# MAAV_RoombaShieldOnly_2V0.net
KiCad netlist of a schematic drawn in EAGLE
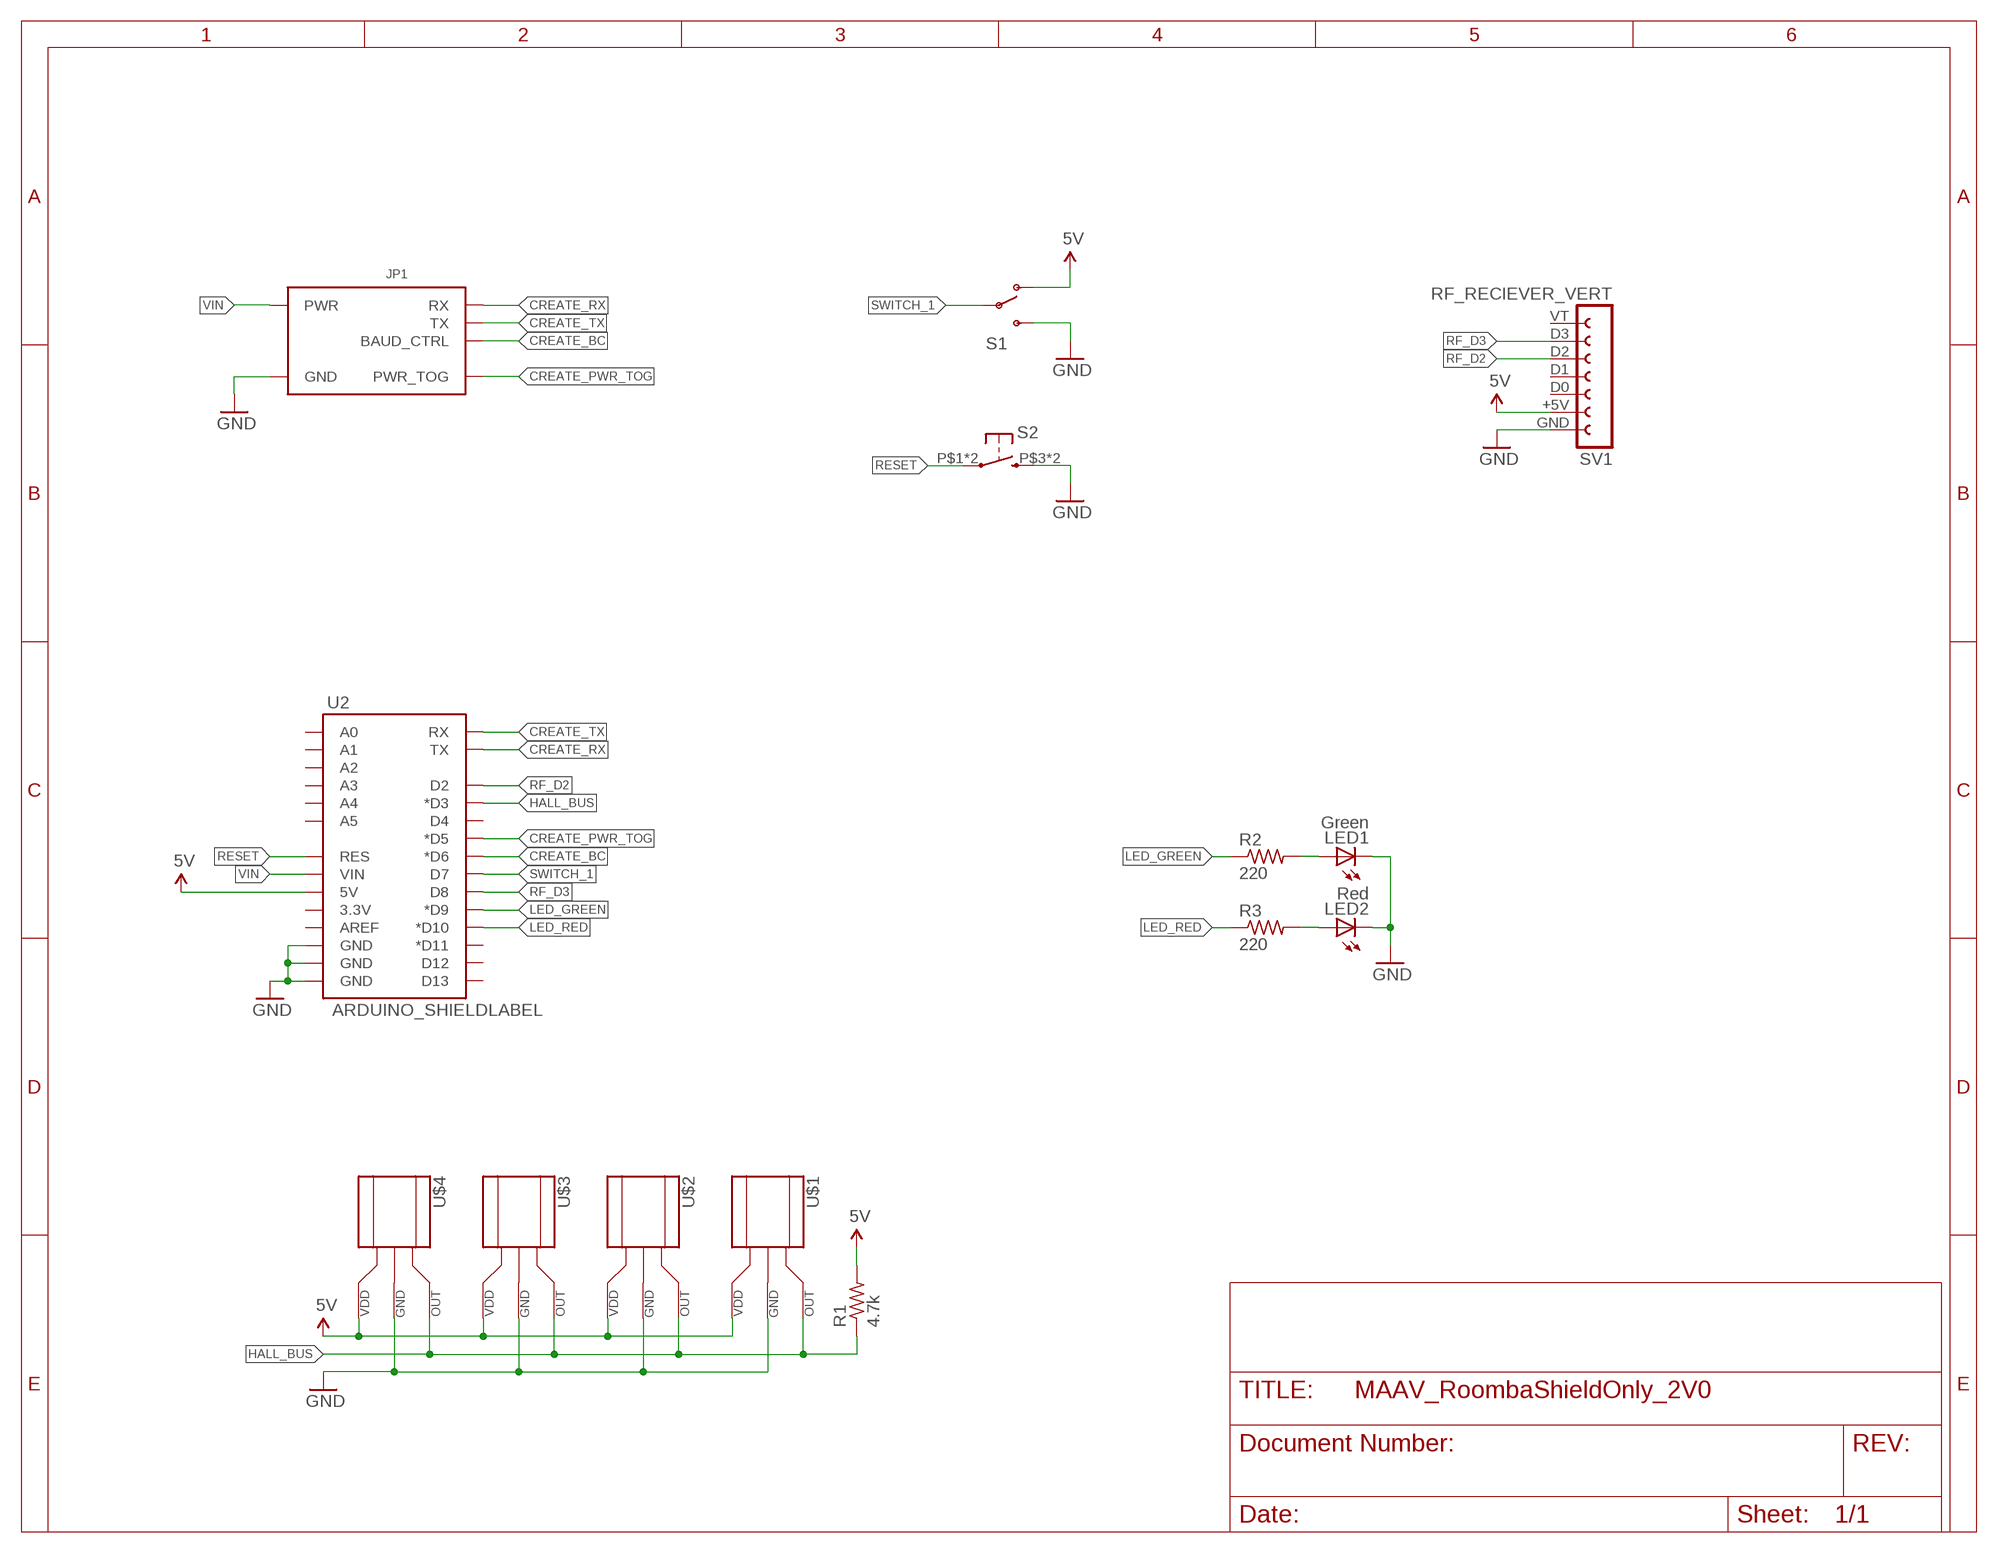
[diagram p0: schematic, sheet 1]

(export (version "E")
  (design (tool "Eeschema 10.0.6"))
  (components
    (comp (ref "JP1")
      (value "IROBOT_CREATE_IARC_HOOKUP")
      (footprint "eagle-import:2X5-SHROUDED")
      (libsource (lib "eagle-import") (part "IROBOT_CREATE_IARC_HOOKUP"))
    )
    (comp (ref "LED1")
      (value "Green")
      (footprint "eagle-import:CHIPLED_0603")
      (libsource (lib "eagle-import") (part "LEDCHIPLED_0603"))
    )
    (comp (ref "LED2")
      (value "Red")
      (footprint "eagle-import:CHIPLED_0603")
      (libsource (lib "eagle-import") (part "LEDCHIPLED_0603"))
    )
    (comp (ref "R1")
      (value "4.7k")
      (footprint "eagle-import:R0603")
      (libsource (lib "eagle-import") (part "R-USR0603"))
    )
    (comp (ref "R2")
      (value "220")
      (footprint "eagle-import:R0603")
      (libsource (lib "eagle-import") (part "R-USR0603"))
    )
    (comp (ref "R3")
      (value "220")
      (footprint "eagle-import:R0603")
      (libsource (lib "eagle-import") (part "R-USR0603"))
    )
    (comp (ref "S1")
      (value "SWITCH-SPDTTHRU-VERT")
      (footprint "eagle-import:SWITCH-SPDT_THRU-VERT")
      (libsource (lib "eagle-import") (part "SWITCH-SPDTTHRU-VERT"))
    )
    (comp (ref "S2")
      (value "TACT_BUTTON_SMD")
      (footprint "eagle-import:SIMPLE_BUTTON_SMD")
      (libsource (lib "eagle-import") (part "TACT_BUTTON_SMD"))
    )
    (comp (ref "SV1")
      (value "RF_RECIEVER_VERT")
      (footprint "eagle-import:RF_RECIEVER_VERT")
      (fields (field (name "MF") "Sulins") (field (name "MPN") "PPTC071LFBN-RC"))
      (libsource (lib "eagle-import") (part "RF_RECIEVER_VERT"))
    )
    (comp (ref "U$1")
      (value "HALL_EFFECTHEADER")
      (footprint "eagle-import:1X03")
      (libsource (lib "eagle-import") (part "HALL_EFFECTHEADER"))
    )
    (comp (ref "U$2")
      (value "HALL_EFFECTHEADER")
      (footprint "eagle-import:1X03")
      (libsource (lib "eagle-import") (part "HALL_EFFECTHEADER"))
    )
    (comp (ref "U$3")
      (value "HALL_EFFECTHEADER")
      (footprint "eagle-import:1X03")
      (libsource (lib "eagle-import") (part "HALL_EFFECTHEADER"))
    )
    (comp (ref "U$4")
      (value "HALL_EFFECTHEADER")
      (footprint "eagle-import:1X03")
      (libsource (lib "eagle-import") (part "HALL_EFFECTHEADER"))
    )
    (comp (ref "U2")
      (value "ARDUINO_SHIELDLABEL")
      (footprint "eagle-import:DUEMILANOVE_SHIELD")
      (libsource (lib "eagle-import") (part "ARDUINO_SHIELDLABEL"))
    )
  )
  (nets
    (net (code "1") (name "5V") (class "Default")
      (node (ref "R1") (pin "2") (pinfunction "2_2") (pintype "passive"))
      (node (ref "S1") (pin "1") (pinfunction "O_1") (pintype "passive"))
      (node (ref "SV1") (pin "+5V") (pinfunction "+5V_+5V") (pintype "power_in"))
      (node (ref "U$1") (pin "1") (pinfunction "VDD_1") (pintype "power_in"))
      (node (ref "U$2") (pin "1") (pinfunction "VDD_1") (pintype "power_in"))
      (node (ref "U$3") (pin "1") (pinfunction "VDD_1") (pintype "power_in"))
      (node (ref "U$4") (pin "1") (pinfunction "VDD_1") (pintype "power_in"))
      (node (ref "U2") (pin "5V") (pinfunction "5V_5V") (pintype "bidirectional"))
    )
    (net (code "2") (name "CREATE_BC") (class "Default")
      (node (ref "JP1") (pin "3") (pinfunction "BAUD_CTRL_3") (pintype "bidirectional"))
      (node (ref "U2") (pin "D6") (pinfunction "*D6_D6") (pintype "bidirectional"))
    )
    (net (code "3") (name "CREATE_PWR_TOG") (class "Default")
      (node (ref "JP1") (pin "5") (pinfunction "PWR_TOG_5") (pintype "bidirectional"))
      (node (ref "U2") (pin "D5") (pinfunction "*D5_D5") (pintype "bidirectional"))
    )
    (net (code "4") (name "CREATE_RX") (class "Default")
      (node (ref "JP1") (pin "4") (pinfunction "RX_4") (pintype "bidirectional"))
      (node (ref "U2") (pin "TX") (pinfunction "TX_TX") (pintype "bidirectional"))
    )
    (net (code "5") (name "CREATE_TX") (class "Default")
      (node (ref "JP1") (pin "1") (pinfunction "TX_1") (pintype "bidirectional"))
      (node (ref "U2") (pin "RX") (pinfunction "RX_RX") (pintype "bidirectional"))
    )
    (net (code "6") (name "GND") (class "Default")
      (node (ref "JP1") (pin "2") (pinfunction "GND_2") (pintype "power_in"))
      (node (ref "LED1") (pin "C") (pinfunction "C_C") (pintype "passive"))
      (node (ref "LED2") (pin "C") (pinfunction "C_C") (pintype "passive"))
      (node (ref "S1") (pin "3") (pinfunction "S_3") (pintype "passive"))
      (node (ref "S2") (pin "P$3") (pinfunction "S_P$3") (pintype "passive"))
      (node (ref "S2") (pin "P$4") (pinfunction "S_P$4") (pintype "passive"))
      (node (ref "SV1") (pin "GND") (pinfunction "GND_GND") (pintype "power_in"))
      (node (ref "U$1") (pin "2") (pinfunction "GND_2") (pintype "power_in"))
      (node (ref "U$2") (pin "2") (pinfunction "GND_2") (pintype "power_in"))
      (node (ref "U$3") (pin "2") (pinfunction "GND_2") (pintype "power_in"))
      (node (ref "U$4") (pin "2") (pinfunction "GND_2") (pintype "power_in"))
      (node (ref "U2") (pin "GND@0") (pinfunction "GND_GND@0") (pintype "bidirectional"))
      (node (ref "U2") (pin "GND@1") (pinfunction "GND_GND@1") (pintype "bidirectional"))
      (node (ref "U2") (pin "GND@2") (pinfunction "GND_GND@2") (pintype "bidirectional"))
    )
    (net (code "7") (name "HALL_BUS") (class "Default")
      (node (ref "R1") (pin "1") (pinfunction "1_1") (pintype "passive"))
      (node (ref "U$1") (pin "3") (pinfunction "OUT_3") (pintype "passive"))
      (node (ref "U$2") (pin "3") (pinfunction "OUT_3") (pintype "passive"))
      (node (ref "U$3") (pin "3") (pinfunction "OUT_3") (pintype "passive"))
      (node (ref "U$4") (pin "3") (pinfunction "OUT_3") (pintype "passive"))
      (node (ref "U2") (pin "D3") (pinfunction "*D3_D3") (pintype "bidirectional"))
    )
    (net (code "8") (name "LED_GREEN") (class "Default")
      (node (ref "R2") (pin "1") (pinfunction "1_1") (pintype "passive"))
      (node (ref "U2") (pin "D9") (pinfunction "*D9_D9") (pintype "bidirectional"))
    )
    (net (code "9") (name "LED_RED") (class "Default")
      (node (ref "R3") (pin "1") (pinfunction "1_1") (pintype "passive"))
      (node (ref "U2") (pin "D10") (pinfunction "*D10_D10") (pintype "bidirectional"))
    )
    (net (code "10") (name "Net-(LED1-PadA)") (class "Default")
      (node (ref "LED1") (pin "A") (pinfunction "A_A") (pintype "passive"))
      (node (ref "R2") (pin "2") (pinfunction "2_2") (pintype "passive"))
    )
    (net (code "11") (name "Net-(LED2-PadA)") (class "Default")
      (node (ref "LED2") (pin "A") (pinfunction "A_A") (pintype "passive"))
      (node (ref "R3") (pin "2") (pinfunction "2_2") (pintype "passive"))
    )
    (net (code "12") (name "RESET") (class "Default")
      (node (ref "S2") (pin "P$1") (pinfunction "P_P$1") (pintype "passive"))
      (node (ref "S2") (pin "P$2") (pinfunction "P_P$2") (pintype "passive"))
      (node (ref "U2") (pin "RES") (pinfunction "RES_RES") (pintype "bidirectional"))
    )
    (net (code "13") (name "RF_D2") (class "Default")
      (node (ref "SV1") (pin "D2") (pinfunction "D2_D2") (pintype "bidirectional"))
      (node (ref "U2") (pin "D2") (pinfunction "D2_D2") (pintype "bidirectional"))
    )
    (net (code "14") (name "RF_D3") (class "Default")
      (node (ref "SV1") (pin "D3") (pinfunction "D3_D3") (pintype "bidirectional"))
      (node (ref "U2") (pin "D8") (pinfunction "D8_D8") (pintype "bidirectional"))
    )
    (net (code "15") (name "SWITCH_1") (class "Default")
      (node (ref "S1") (pin "2") (pinfunction "P_2") (pintype "passive"))
      (node (ref "U2") (pin "D7") (pinfunction "D7_D7") (pintype "bidirectional"))
    )
    (net (code "16") (name "VIN") (class "Default")
      (node (ref "JP1") (pin "6") (pinfunction "PWR_6") (pintype "power_in"))
      (node (ref "U2") (pin "VIN") (pinfunction "VIN_VIN") (pintype "bidirectional"))
    )
    (net (code "17") (name "unconnected-(SV1-PadD0)") (class "Default")
      (node (ref "SV1") (pin "D0") (pinfunction "D0_D0") (pintype "bidirectional"))
    )
    (net (code "18") (name "unconnected-(SV1-PadD1)") (class "Default")
      (node (ref "SV1") (pin "D1") (pinfunction "D1_D1") (pintype "bidirectional"))
    )
    (net (code "19") (name "unconnected-(SV1-PadVT)") (class "Default")
      (node (ref "SV1") (pin "VT") (pinfunction "VT_VT") (pintype "passive"))
    )
    (net (code "20") (name "unconnected-(U2-*D11-PadD11)") (class "Default")
      (node (ref "U2") (pin "D11") (pinfunction "*D11_D11") (pintype "bidirectional"))
    )
    (net (code "21") (name "unconnected-(U2-Pad3.3V)") (class "Default")
      (node (ref "U2") (pin "3.3V") (pinfunction "3.3V_3.3V") (pintype "bidirectional"))
    )
    (net (code "22") (name "unconnected-(U2-PadA0)") (class "Default")
      (node (ref "U2") (pin "A0") (pinfunction "A0_A0") (pintype "bidirectional"))
    )
    (net (code "23") (name "unconnected-(U2-PadA1)") (class "Default")
      (node (ref "U2") (pin "A1") (pinfunction "A1_A1") (pintype "bidirectional"))
    )
    (net (code "24") (name "unconnected-(U2-PadA2)") (class "Default")
      (node (ref "U2") (pin "A2") (pinfunction "A2_A2") (pintype "bidirectional"))
    )
    (net (code "25") (name "unconnected-(U2-PadA3)") (class "Default")
      (node (ref "U2") (pin "A3") (pinfunction "A3_A3") (pintype "bidirectional"))
    )
    (net (code "26") (name "unconnected-(U2-PadA4)") (class "Default")
      (node (ref "U2") (pin "A4") (pinfunction "A4_A4") (pintype "bidirectional"))
    )
    (net (code "27") (name "unconnected-(U2-PadA5)") (class "Default")
      (node (ref "U2") (pin "A5") (pinfunction "A5_A5") (pintype "bidirectional"))
    )
    (net (code "28") (name "unconnected-(U2-PadAREF)") (class "Default")
      (node (ref "U2") (pin "AREF") (pinfunction "AREF_AREF") (pintype "bidirectional"))
    )
    (net (code "29") (name "unconnected-(U2-PadD4)") (class "Default")
      (node (ref "U2") (pin "D4") (pinfunction "D4_D4") (pintype "bidirectional"))
    )
    (net (code "30") (name "unconnected-(U2-PadD12)") (class "Default")
      (node (ref "U2") (pin "D12") (pinfunction "D12_D12") (pintype "bidirectional"))
    )
    (net (code "31") (name "unconnected-(U2-PadD13)") (class "Default")
      (node (ref "U2") (pin "D13") (pinfunction "D13_D13") (pintype "bidirectional"))
    )
  )
)
